# tiny_robot_rene_smd.net
KiCad netlist of a schematic drawn in EAGLE
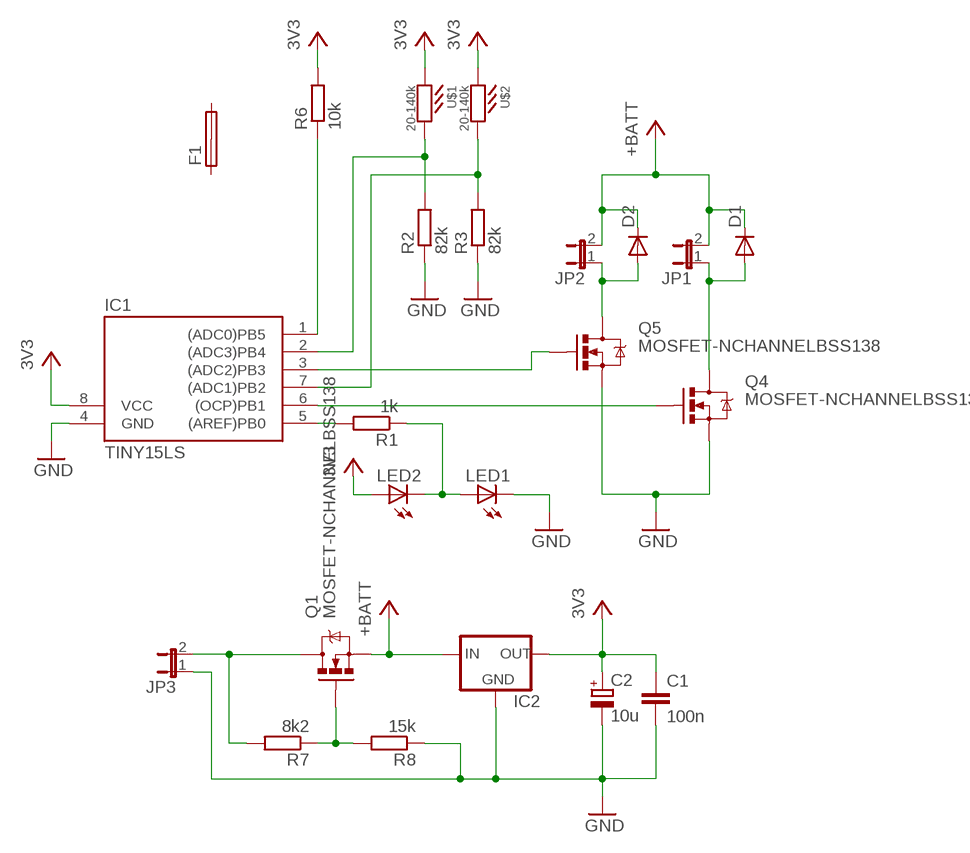
[diagram p0: schematic, sheet 1]

(export (version "E")
  (design (tool "Eeschema 10.0.6"))
  (components
    (comp (ref "C1")
      (value "100n")
      (footprint "eagle-import:C0805K")
      (libsource (lib "eagle-import") (part "C-EUC0805K"))
    )
    (comp (ref "C2")
      (value "10u")
      (footprint "eagle-import:SANYO-OSCON_SMD_A5")
      (libsource (lib "eagle-import") (part "CPOL-EUSANYO_SMD_A5"))
    )
    (comp (ref "D1")
      (value "DIODE-MINIMELF")
      (footprint "eagle-import:MINIMELF")
      (libsource (lib "eagle-import") (part "DIODE-MINIMELF"))
    )
    (comp (ref "D2")
      (value "DIODE-MINIMELF")
      (footprint "eagle-import:MINIMELF")
      (libsource (lib "eagle-import") (part "DIODE-MINIMELF"))
    )
    (comp (ref "F1")
      (value "SHK20L")
      (footprint "eagle-import:SHK20L")
      (libsource (lib "eagle-import") (part "SHK20L"))
    )
    (comp (ref "IC1")
      (value "TINY15LS")
      (footprint "eagle-import:SOIC8")
      (libsource (lib "eagle-import") (part "TINY15LS"))
    )
    (comp (ref "IC2")
      (value "MCP1700SMD")
      (footprint "eagle-import:SOT23")
      (libsource (lib "eagle-import") (part "MCP1700SMD"))
    )
    (comp (ref "JP1")
      (value "JP1E")
      (footprint "eagle-import:JP1")
      (libsource (lib "eagle-import") (part "JP1E"))
    )
    (comp (ref "JP2")
      (value "JP1E")
      (footprint "eagle-import:JP1")
      (libsource (lib "eagle-import") (part "JP1E"))
    )
    (comp (ref "JP3")
      (value "JP1E")
      (footprint "eagle-import:JP1")
      (libsource (lib "eagle-import") (part "JP1E"))
    )
    (comp (ref "LED1")
      (value "LEDCHIPLED_0805")
      (footprint "eagle-import:CHIPLED_0805")
      (libsource (lib "eagle-import") (part "LEDCHIPLED_0805"))
    )
    (comp (ref "LED2")
      (value "LEDCHIPLED_0805")
      (footprint "eagle-import:CHIPLED_0805")
      (libsource (lib "eagle-import") (part "LEDCHIPLED_0805"))
    )
    (comp (ref "Q1")
      (value "MOSFET-NCHANNELBSS138")
      (footprint "eagle-import:SOT23")
      (fields (field (name "PROD_ID") "TRANS-00830"))
      (libsource (lib "eagle-import") (part "MOSFET-NCHANNELBSS138"))
    )
    (comp (ref "Q4")
      (value "MOSFET-NCHANNELBSS138")
      (footprint "eagle-import:SOT23")
      (libsource (lib "eagle-import") (part "MOSFET-NCHANNELBSS138"))
    )
    (comp (ref "Q5")
      (value "MOSFET-NCHANNELBSS138")
      (footprint "eagle-import:SOT23")
      (libsource (lib "eagle-import") (part "MOSFET-NCHANNELBSS138"))
    )
    (comp (ref "R1")
      (value "1k")
      (footprint "eagle-import:M1206")
      (libsource (lib "eagle-import") (part "R-EU_M1206"))
    )
    (comp (ref "R2")
      (value "82k")
      (footprint "eagle-import:M1206")
      (libsource (lib "eagle-import") (part "R-EU_M1206"))
    )
    (comp (ref "R3")
      (value "82k")
      (footprint "eagle-import:M1206")
      (libsource (lib "eagle-import") (part "R-EU_M1206"))
    )
    (comp (ref "R6")
      (value "10k")
      (footprint "eagle-import:M1206")
      (libsource (lib "eagle-import") (part "R-EU_M1206"))
    )
    (comp (ref "R7")
      (value "8k2")
      (footprint "eagle-import:M0805")
      (libsource (lib "eagle-import") (part "R-EU_M0805"))
    )
    (comp (ref "R8")
      (value "15k")
      (footprint "eagle-import:M0805")
      (libsource (lib "eagle-import") (part "R-EU_M0805"))
    )
    (comp (ref "U$1")
      (value "20-140k")
      (footprint "eagle-import:LDR-906014")
      (libsource (lib "eagle-import") (part "LDR-906014"))
    )
    (comp (ref "U$2")
      (value "20-140k")
      (footprint "eagle-import:LDR-906014")
      (libsource (lib "eagle-import") (part "LDR-906014"))
    )
  )
  (nets
    (net (code "1") (name "+BATT") (class "Default")
      (node (ref "D1") (pin "C") (pinfunction "C_C") (pintype "passive"))
      (node (ref "D2") (pin "C") (pinfunction "C_C") (pintype "passive"))
      (node (ref "IC2") (pin "3") (pinfunction "IN_3") (pintype "input"))
      (node (ref "JP1") (pin "2") (pinfunction "2_2") (pintype "passive"))
      (node (ref "JP2") (pin "2") (pinfunction "2_2") (pintype "passive"))
      (node (ref "Q1") (pin "2") (pinfunction "S_2") (pintype "passive"))
    )
    (net (code "2") (name "3V3") (class "Default")
      (node (ref "C1") (pin "1") (pinfunction "1_1") (pintype "passive"))
      (node (ref "C2") (pin "+") (pinfunction "+_+") (pintype "passive"))
      (node (ref "IC1") (pin "8") (pinfunction "VCC_8") (pintype "power_in"))
      (node (ref "IC2") (pin "2") (pinfunction "OUT_2") (pintype "passive"))
      (node (ref "LED2") (pin "A") (pinfunction "A_A") (pintype "passive"))
      (node (ref "R6") (pin "2") (pinfunction "2_2") (pintype "passive"))
      (node (ref "U$1") (pin "P$1") (pinfunction "P$1_P$1") (pintype "passive"))
      (node (ref "U$2") (pin "P$1") (pinfunction "P$1_P$1") (pintype "passive"))
    )
    (net (code "3") (name "GND") (class "Default")
      (node (ref "C1") (pin "2") (pinfunction "2_2") (pintype "passive"))
      (node (ref "C2") (pin "-") (pinfunction "-_-") (pintype "passive"))
      (node (ref "IC1") (pin "4") (pinfunction "GND_4") (pintype "power_in"))
      (node (ref "IC2") (pin "1") (pinfunction "GND_1") (pintype "input"))
      (node (ref "JP3") (pin "1") (pinfunction "1_1") (pintype "passive"))
      (node (ref "LED1") (pin "C") (pinfunction "C_C") (pintype "passive"))
      (node (ref "Q4") (pin "2") (pinfunction "S_2") (pintype "passive"))
      (node (ref "Q5") (pin "2") (pinfunction "S_2") (pintype "passive"))
      (node (ref "R2") (pin "1") (pinfunction "1_1") (pintype "passive"))
      (node (ref "R3") (pin "1") (pinfunction "1_1") (pintype "passive"))
      (node (ref "R8") (pin "1") (pinfunction "1_1") (pintype "passive"))
    )
    (net (code "4") (name "Net-(IC1-(ADC0)PB5)") (class "Default")
      (node (ref "IC1") (pin "1") (pinfunction "(ADC0)PB5_1") (pintype "bidirectional"))
      (node (ref "R6") (pin "1") (pinfunction "1_1") (pintype "passive"))
    )
    (net (code "5") (name "Net-(IC1-(ADC1)PB2)") (class "Default")
      (node (ref "IC1") (pin "7") (pinfunction "(ADC1)PB2_7") (pintype "bidirectional"))
      (node (ref "R3") (pin "2") (pinfunction "2_2") (pintype "passive"))
      (node (ref "U$2") (pin "P$2") (pinfunction "P$2_P$2") (pintype "passive"))
    )
    (net (code "6") (name "Net-(IC1-(ADC2)PB3)") (class "Default")
      (node (ref "IC1") (pin "3") (pinfunction "(ADC2)PB3_3") (pintype "bidirectional"))
      (node (ref "Q5") (pin "1") (pinfunction "G_1") (pintype "passive"))
    )
    (net (code "7") (name "Net-(IC1-(ADC3)PB4)") (class "Default")
      (node (ref "IC1") (pin "2") (pinfunction "(ADC3)PB4_2") (pintype "bidirectional"))
      (node (ref "R2") (pin "2") (pinfunction "2_2") (pintype "passive"))
      (node (ref "U$1") (pin "P$2") (pinfunction "P$2_P$2") (pintype "passive"))
    )
    (net (code "8") (name "Net-(IC1-(AREF)PB0)") (class "Default")
      (node (ref "IC1") (pin "5") (pinfunction "(AREF)PB0_5") (pintype "bidirectional"))
      (node (ref "R1") (pin "2") (pinfunction "2_2") (pintype "passive"))
    )
    (net (code "9") (name "Net-(IC1-(OCP)PB1)") (class "Default")
      (node (ref "IC1") (pin "6") (pinfunction "(OCP)PB1_6") (pintype "bidirectional"))
      (node (ref "Q4") (pin "1") (pinfunction "G_1") (pintype "passive"))
    )
    (net (code "10") (name "Net-(LED1-PadA)") (class "Default")
      (node (ref "LED1") (pin "A") (pinfunction "A_A") (pintype "passive"))
      (node (ref "LED2") (pin "C") (pinfunction "C_C") (pintype "passive"))
      (node (ref "R1") (pin "1") (pinfunction "1_1") (pintype "passive"))
    )
    (net (code "11") (name "Net-(Q1-D)") (class "Default")
      (node (ref "JP3") (pin "2") (pinfunction "2_2") (pintype "passive"))
      (node (ref "Q1") (pin "3") (pinfunction "D_3") (pintype "passive"))
      (node (ref "R7") (pin "2") (pinfunction "2_2") (pintype "passive"))
    )
    (net (code "12") (name "Net-(Q1-G)") (class "Default")
      (node (ref "Q1") (pin "1") (pinfunction "G_1") (pintype "passive"))
      (node (ref "R7") (pin "1") (pinfunction "1_1") (pintype "passive"))
      (node (ref "R8") (pin "2") (pinfunction "2_2") (pintype "passive"))
    )
    (net (code "13") (name "Net-(Q4-D)") (class "Default")
      (node (ref "D1") (pin "A") (pinfunction "A_A") (pintype "passive"))
      (node (ref "JP1") (pin "1") (pinfunction "1_1") (pintype "passive"))
      (node (ref "Q4") (pin "3") (pinfunction "D_3") (pintype "passive"))
    )
    (net (code "14") (name "Net-(Q5-D)") (class "Default")
      (node (ref "D2") (pin "A") (pinfunction "A_A") (pintype "passive"))
      (node (ref "JP2") (pin "1") (pinfunction "1_1") (pintype "passive"))
      (node (ref "Q5") (pin "3") (pinfunction "D_3") (pintype "passive"))
    )
    (net (code "15") (name "unconnected-(F1-Pad1A)") (class "Default")
      (node (ref "F1") (pin "1A") (pinfunction "1A_1A") (pintype "passive"))
    )
    (net (code "16") (name "unconnected-(F1-Pad1B)") (class "Default")
      (node (ref "F1") (pin "1B") (pinfunction "1B_1B") (pintype "passive"))
    )
    (net (code "17") (name "unconnected-(F1-Pad2A)") (class "Default")
      (node (ref "F1") (pin "2A") (pinfunction "2A_2A") (pintype "passive"))
    )
    (net (code "18") (name "unconnected-(F1-Pad2B)") (class "Default")
      (node (ref "F1") (pin "2B") (pinfunction "2B_2B") (pintype "passive"))
    )
  )
)
